# Transmitter_edge_trigger.net
KiCad netlist of a schematic drawn in EAGLE
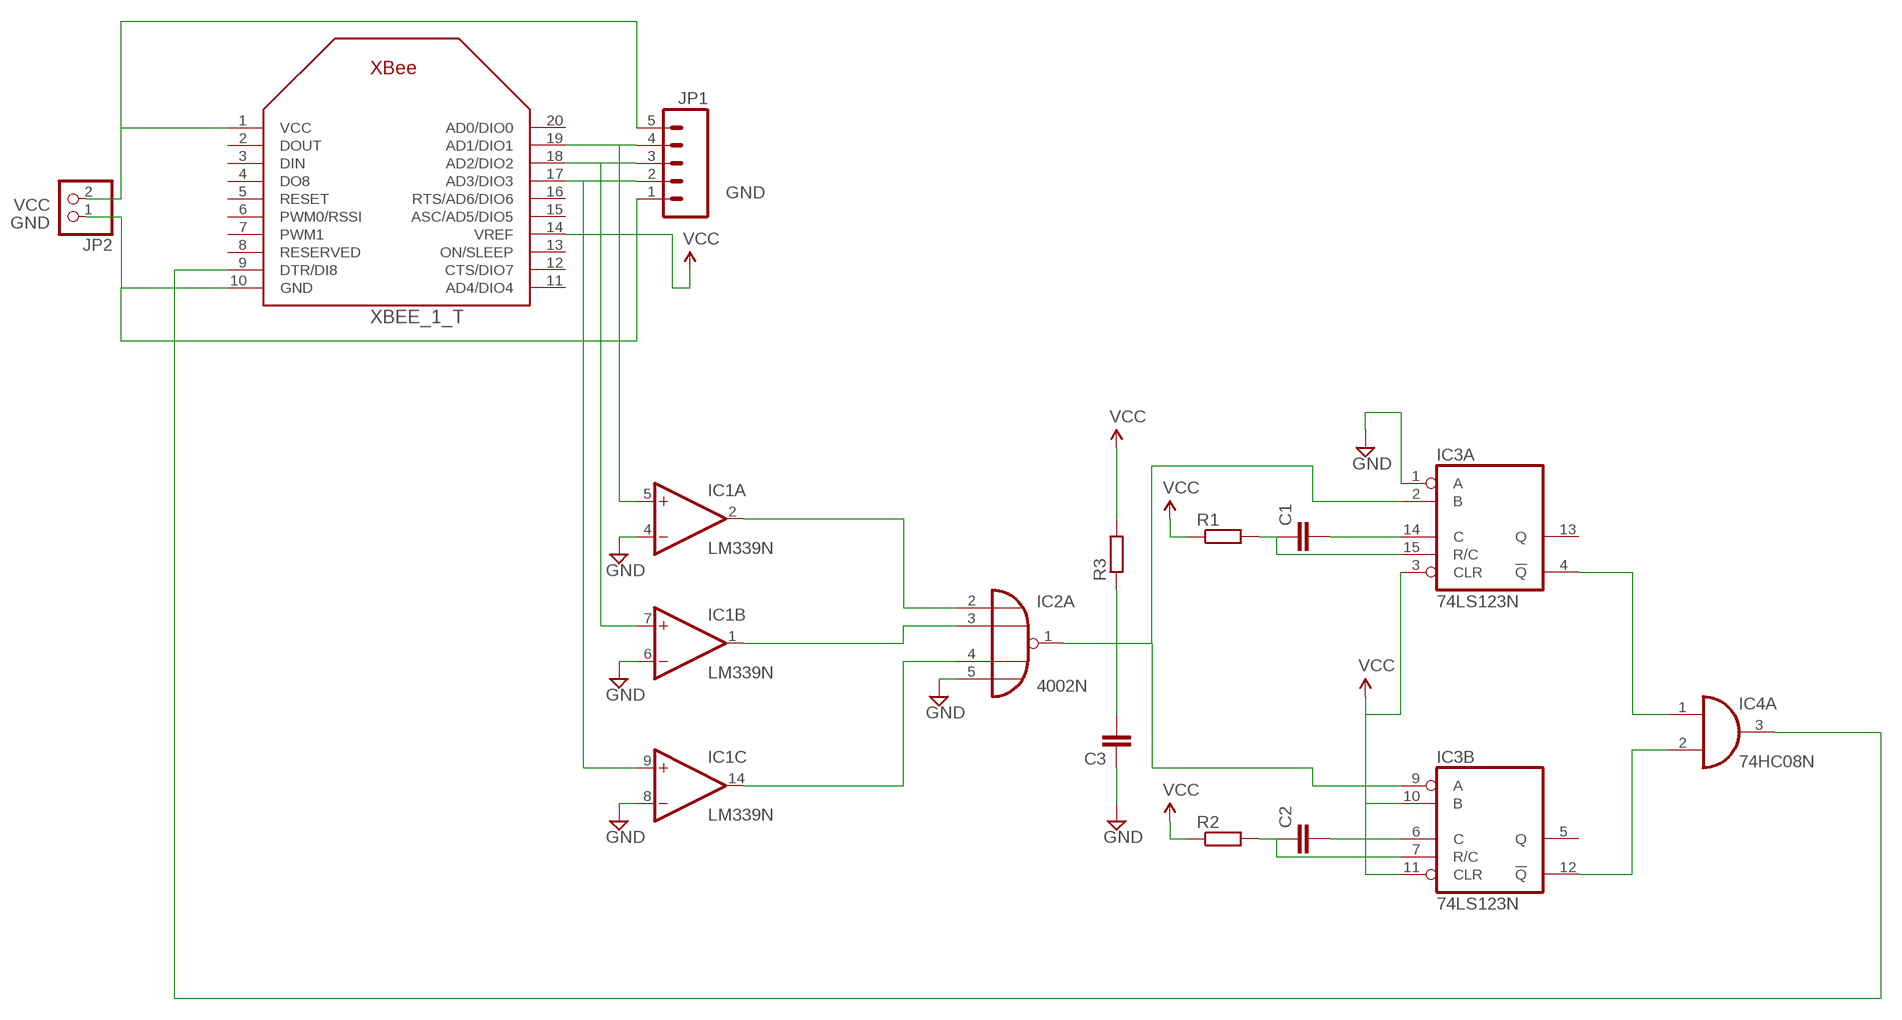
[diagram p0: schematic, sheet 1]

(export (version "E")
  (design (tool "Eeschema 10.0.6"))
  (components
    (comp (ref "C1")
      (value "C-EU025-030X050")
      (footprint "eagle-import:C025-030X050")
      (libsource (lib "eagle-import") (part "C-EU025-030X050"))
    )
    (comp (ref "C2")
      (value "C-EU025-030X050")
      (footprint "eagle-import:C025-030X050")
      (libsource (lib "eagle-import") (part "C-EU025-030X050"))
    )
    (comp (ref "C3")
      (value "C-EU025-030X050")
      (footprint "eagle-import:C025-030X050")
      (libsource (lib "eagle-import") (part "C-EU025-030X050"))
    )
    (comp (ref "IC1")
      (value "LM339N")
      (footprint "eagle-import:DIL14")
      (libsource (lib "eagle-import") (part "LM339N"))
    )
    (comp (ref "IC2")
      (value "4002N")
      (footprint "eagle-import:DIL14")
      (libsource (lib "eagle-import") (part "4002N"))
    )
    (comp (ref "IC3")
      (value "74LS123N")
      (footprint "eagle-import:DIL16")
      (libsource (lib "eagle-import") (part "74123NLS"))
    )
    (comp (ref "IC4")
      (value "74HC08N")
      (footprint "eagle-import:DIL14")
      (libsource (lib "eagle-import") (part "7408NHC"))
    )
    (comp (ref "JP1")
      (value "M05PTH")
      (footprint "eagle-import:1X05")
      (libsource (lib "eagle-import") (part "M05PTH"))
    )
    (comp (ref "JP2")
      (value "PINHD-1X2")
      (footprint "eagle-import:1X02")
      (libsource (lib "eagle-import") (part "PINHD-1X2"))
    )
    (comp (ref "R1")
      (value "R-EU_0207/12")
      (footprint "eagle-import:0207_12")
      (libsource (lib "eagle-import") (part "R-EU_0207/12"))
    )
    (comp (ref "R2")
      (value "R-EU_0207/12")
      (footprint "eagle-import:0207_12")
      (libsource (lib "eagle-import") (part "R-EU_0207/12"))
    )
    (comp (ref "R3")
      (value "R-EU_0207/12")
      (footprint "eagle-import:0207_12")
      (libsource (lib "eagle-import") (part "R-EU_0207/12"))
    )
    (comp (ref "XBEE_1_T")
      (value "XBEE")
      (footprint "eagle-import:XBEE")
      (libsource (lib "eagle-import") (part "XBEE"))
    )
  )
  (nets
    (net (code "1") (name "GND") (class "Default")
      (node (ref "C3") (pin "1") (pinfunction "1_1") (pintype "passive"))
      (node (ref "IC1") (pin "4") (pinfunction "-IN_4") (pintype "input"))
      (node (ref "IC1") (pin "6") (pinfunction "-IN_6") (pintype "input"))
      (node (ref "IC1") (pin "8") (pinfunction "-IN_8") (pintype "input"))
      (node (ref "IC2") (pin "5") (pinfunction "I3_5") (pintype "input"))
      (node (ref "IC3") (pin "1") (pinfunction "A_1") (pintype "input"))
      (node (ref "JP1") (pin "1") (pinfunction "1_1") (pintype "passive"))
      (node (ref "JP2") (pin "1") (pinfunction "1_1") (pintype "passive"))
      (node (ref "XBEE_1_T") (pin "10") (pinfunction "GND_10") (pintype "power_in"))
    )
    (net (code "2") (name "Net-(IC1A-+IN)") (class "Default")
      (node (ref "IC1") (pin "5") (pinfunction "+IN_5") (pintype "input"))
      (node (ref "JP1") (pin "4") (pinfunction "4_4") (pintype "passive"))
      (node (ref "XBEE_1_T") (pin "19") (pinfunction "AD1/DIO1_19") (pintype "bidirectional"))
    )
    (net (code "3") (name "Net-(IC1A-OUT)") (class "Default")
      (node (ref "IC1") (pin "2") (pinfunction "OUT_2") (pintype "open_collector"))
      (node (ref "IC2") (pin "2") (pinfunction "I0_2") (pintype "input"))
    )
    (net (code "4") (name "Net-(IC1B-+IN)") (class "Default")
      (node (ref "IC1") (pin "7") (pinfunction "+IN_7") (pintype "input"))
      (node (ref "JP1") (pin "3") (pinfunction "3_3") (pintype "passive"))
      (node (ref "XBEE_1_T") (pin "18") (pinfunction "AD2/DIO2_18") (pintype "bidirectional"))
    )
    (net (code "5") (name "Net-(IC1B-OUT)") (class "Default")
      (node (ref "IC1") (pin "1") (pinfunction "OUT_1") (pintype "open_collector"))
      (node (ref "IC2") (pin "3") (pinfunction "I1_3") (pintype "input"))
    )
    (net (code "6") (name "Net-(IC1C-+IN)") (class "Default")
      (node (ref "IC1") (pin "9") (pinfunction "+IN_9") (pintype "input"))
      (node (ref "JP1") (pin "2") (pinfunction "2_2") (pintype "passive"))
      (node (ref "XBEE_1_T") (pin "17") (pinfunction "AD3/DIO3_17") (pintype "bidirectional"))
    )
    (net (code "7") (name "Net-(IC1C-OUT)") (class "Default")
      (node (ref "IC1") (pin "14") (pinfunction "OUT_14") (pintype "open_collector"))
      (node (ref "IC2") (pin "4") (pinfunction "I2_4") (pintype "input"))
    )
    (net (code "8") (name "Net-(IC2A-O)") (class "Default")
      (node (ref "C3") (pin "2") (pinfunction "2_2") (pintype "passive"))
      (node (ref "IC2") (pin "1") (pinfunction "O_1") (pintype "output"))
      (node (ref "IC3") (pin "2") (pinfunction "B_2") (pintype "input"))
      (node (ref "IC3") (pin "9") (pinfunction "A_9") (pintype "input"))
      (node (ref "R3") (pin "1") (pinfunction "1_1") (pintype "passive"))
    )
    (net (code "9") (name "Net-(IC3A-C)") (class "Default")
      (node (ref "C1") (pin "2") (pinfunction "2_2") (pintype "passive"))
      (node (ref "IC3") (pin "14") (pinfunction "C_14") (pintype "input"))
    )
    (net (code "10") (name "Net-(IC3A-R{slash}C)") (class "Default")
      (node (ref "C1") (pin "1") (pinfunction "1_1") (pintype "passive"))
      (node (ref "IC3") (pin "15") (pinfunction "R/C_15") (pintype "input"))
      (node (ref "R1") (pin "2") (pinfunction "2_2") (pintype "passive"))
    )
    (net (code "11") (name "Net-(IC3A-~{Q})") (class "Default")
      (node (ref "IC3") (pin "4") (pinfunction "~{Q}_4") (pintype "output"))
      (node (ref "IC4") (pin "1") (pinfunction "I0_1") (pintype "input"))
    )
    (net (code "12") (name "Net-(IC3B-C)") (class "Default")
      (node (ref "C2") (pin "2") (pinfunction "2_2") (pintype "passive"))
      (node (ref "IC3") (pin "6") (pinfunction "C_6") (pintype "input"))
    )
    (net (code "13") (name "Net-(IC3B-R{slash}C)") (class "Default")
      (node (ref "C2") (pin "1") (pinfunction "1_1") (pintype "passive"))
      (node (ref "IC3") (pin "7") (pinfunction "R/C_7") (pintype "input"))
      (node (ref "R2") (pin "2") (pinfunction "2_2") (pintype "passive"))
    )
    (net (code "14") (name "Net-(IC3B-~{Q})") (class "Default")
      (node (ref "IC3") (pin "12") (pinfunction "~{Q}_12") (pintype "output"))
      (node (ref "IC4") (pin "2") (pinfunction "I1_2") (pintype "input"))
    )
    (net (code "15") (name "Net-(IC4A-O)") (class "Default")
      (node (ref "IC4") (pin "3") (pinfunction "O_3") (pintype "output"))
      (node (ref "XBEE_1_T") (pin "9") (pinfunction "DTR/DI8_9") (pintype "input"))
    )
    (net (code "16") (name "VCC") (class "Default")
      (node (ref "IC3") (pin "10") (pinfunction "B_10") (pintype "input"))
      (node (ref "IC3") (pin "11") (pinfunction "CLR_11") (pintype "input"))
      (node (ref "IC3") (pin "3") (pinfunction "CLR_3") (pintype "input"))
      (node (ref "JP1") (pin "5") (pinfunction "5_5") (pintype "passive"))
      (node (ref "JP2") (pin "2") (pinfunction "2_2") (pintype "passive"))
      (node (ref "R1") (pin "1") (pinfunction "1_1") (pintype "passive"))
      (node (ref "R2") (pin "1") (pinfunction "1_1") (pintype "passive"))
      (node (ref "R3") (pin "2") (pinfunction "2_2") (pintype "passive"))
      (node (ref "XBEE_1_T") (pin "1") (pinfunction "VCC_1") (pintype "power_in"))
      (node (ref "XBEE_1_T") (pin "14") (pinfunction "VREF_14") (pintype "input"))
    )
    (net (code "17") (name "unconnected-(IC3A-Q-Pad13)") (class "Default")
      (node (ref "IC3") (pin "13") (pinfunction "Q_13") (pintype "output"))
    )
    (net (code "18") (name "unconnected-(IC3B-Q-Pad5)") (class "Default")
      (node (ref "IC3") (pin "5") (pinfunction "Q_5") (pintype "output"))
    )
    (net (code "19") (name "unconnected-(XBEE_1_T-AD0{slash}DIO0-Pad20)") (class "Default")
      (node (ref "XBEE_1_T") (pin "20") (pinfunction "AD0/DIO0_20") (pintype "bidirectional"))
    )
    (net (code "20") (name "unconnected-(XBEE_1_T-AD4{slash}DIO4-Pad11)") (class "Default")
      (node (ref "XBEE_1_T") (pin "11") (pinfunction "AD4/DIO4_11") (pintype "bidirectional"))
    )
    (net (code "21") (name "unconnected-(XBEE_1_T-ASC{slash}AD5{slash}DIO5-Pad15)") (class "Default")
      (node (ref "XBEE_1_T") (pin "15") (pinfunction "ASC/AD5/DIO5_15") (pintype "bidirectional"))
    )
    (net (code "22") (name "unconnected-(XBEE_1_T-CTS{slash}DIO7-Pad12)") (class "Default")
      (node (ref "XBEE_1_T") (pin "12") (pinfunction "CTS/DIO7_12") (pintype "bidirectional"))
    )
    (net (code "23") (name "unconnected-(XBEE_1_T-DIN-Pad3)") (class "Default")
      (node (ref "XBEE_1_T") (pin "3") (pinfunction "DIN_3") (pintype "input"))
    )
    (net (code "24") (name "unconnected-(XBEE_1_T-DO8-Pad4)") (class "Default")
      (node (ref "XBEE_1_T") (pin "4") (pinfunction "DO8_4") (pintype "output"))
    )
    (net (code "25") (name "unconnected-(XBEE_1_T-DOUT-Pad2)") (class "Default")
      (node (ref "XBEE_1_T") (pin "2") (pinfunction "DOUT_2") (pintype "output"))
    )
    (net (code "26") (name "unconnected-(XBEE_1_T-ON{slash}SLEEP-Pad13)") (class "Default")
      (node (ref "XBEE_1_T") (pin "13") (pinfunction "ON/SLEEP_13") (pintype "output"))
    )
    (net (code "27") (name "unconnected-(XBEE_1_T-PWM0{slash}RSSI-Pad6)") (class "Default")
      (node (ref "XBEE_1_T") (pin "6") (pinfunction "PWM0/RSSI_6") (pintype "output"))
    )
    (net (code "28") (name "unconnected-(XBEE_1_T-PWM1-Pad7)") (class "Default")
      (node (ref "XBEE_1_T") (pin "7") (pinfunction "PWM1_7") (pintype "output"))
    )
    (net (code "29") (name "unconnected-(XBEE_1_T-RESERVED-Pad8)") (class "Default")
      (node (ref "XBEE_1_T") (pin "8") (pinfunction "RESERVED_8") (pintype "no_connect"))
    )
    (net (code "30") (name "unconnected-(XBEE_1_T-RESET-Pad5)") (class "Default")
      (node (ref "XBEE_1_T") (pin "5") (pinfunction "RESET_5") (pintype "input"))
    )
    (net (code "31") (name "unconnected-(XBEE_1_T-RTS{slash}AD6{slash}DIO6-Pad16)") (class "Default")
      (node (ref "XBEE_1_T") (pin "16") (pinfunction "RTS/AD6/DIO6_16") (pintype "bidirectional"))
    )
  )
)
